# arduinoBasic.net
KiCad netlist of a schematic drawn in EAGLE
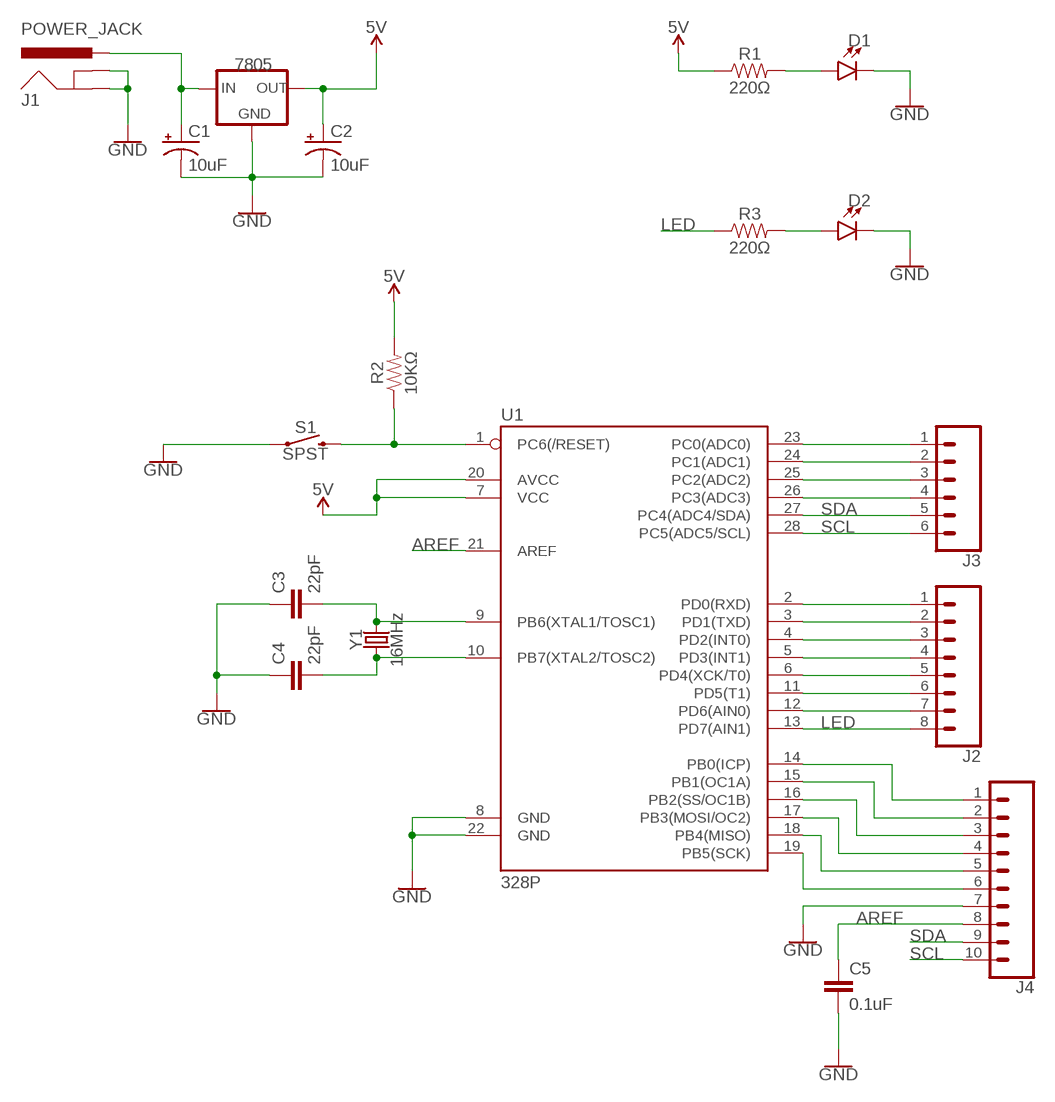
[diagram p0: schematic, sheet 1]

(export (version "E")
  (design (tool "Eeschema 10.0.6"))
  (components
    (comp (ref "7805")
      (value "V_REG_78XXSINK")
      (footprint "eagle-import:TO220-IGO")
      (libsource (lib "eagle-import") (part "V_REG_78XXSINK"))
    )
    (comp (ref "C1")
      (value "10uF")
      (footprint "eagle-import:CPOL-RADIAL-2.5MM-5MM")
      (libsource (lib "eagle-import") (part "10UF-POLAR-RADIAL-2.5MM-25V-20%"))
    )
    (comp (ref "C2")
      (value "10uF")
      (footprint "eagle-import:CPOL-RADIAL-2.5MM-5MM")
      (libsource (lib "eagle-import") (part "10UF-POLAR-RADIAL-2.5MM-25V-20%"))
    )
    (comp (ref "C3")
      (value "22pF")
      (footprint "eagle-import:CAP-PTH-2.54")
      (libsource (lib "eagle-import") (part "22PF-PTH-2.54MM-200V-5%"))
    )
    (comp (ref "C4")
      (value "22pF")
      (footprint "eagle-import:CAP-PTH-2.54")
      (libsource (lib "eagle-import") (part "22PF-PTH-2.54MM-200V-5%"))
    )
    (comp (ref "C5")
      (value "0.1uF")
      (footprint "eagle-import:CAP-PTH-SMALL-KIT")
      (libsource (lib "eagle-import") (part "0.1UF-KIT-EZ-50V-20%"))
    )
    (comp (ref "D1")
      (value "LED5MM")
      (footprint "eagle-import:LED_5MM")
      (libsource (lib "eagle-import") (part "LED5MM"))
    )
    (comp (ref "D2")
      (value "LED5MM")
      (footprint "eagle-import:LED_5MM")
      (libsource (lib "eagle-import") (part "LED5MM"))
    )
    (comp (ref "J1")
      (value "POWER_JACK")
      (footprint "eagle-import:POWER_JACK_PTH")
      (libsource (lib "eagle-import") (part "POWER_JACK"))
    )
    (comp (ref "J2")
      (value "CONN_08\"")
      (footprint "eagle-import:1X08")
      (libsource (lib "eagle-import") (part "CONN_08{dblquote}"))
    )
    (comp (ref "J3")
      (value "CONN_06SILK_FEMALE_PTH")
      (footprint "eagle-import:1X06")
      (libsource (lib "eagle-import") (part "CONN_06SILK_FEMALE_PTH"))
    )
    (comp (ref "J4")
      (value "CONN_10\"")
      (footprint "eagle-import:1X10")
      (libsource (lib "eagle-import") (part "CONN_10{dblquote}"))
    )
    (comp (ref "R1")
      (value "220Ω")
      (footprint "eagle-import:AXIAL-0.3")
      (libsource (lib "eagle-import") (part "RESISTORAXIAL-0.3"))
    )
    (comp (ref "R2")
      (value "10KΩ")
      (footprint "eagle-import:AXIAL-0.3")
      (libsource (lib "eagle-import") (part "RESISTORAXIAL-0.3"))
    )
    (comp (ref "R3")
      (value "220Ω")
      (footprint "eagle-import:AXIAL-0.3")
      (libsource (lib "eagle-import") (part "RESISTORAXIAL-0.3"))
    )
    (comp (ref "S1")
      (value "SPST")
      (footprint "eagle-import:TACTILE_SWITCH_PTH_12MM")
      (libsource (lib "eagle-import") (part "MOMENTARY-SWITCH-SPST-PTH-12MM"))
    )
    (comp (ref "U1")
      (value "328P")
      (footprint "eagle-import:DIP28")
      (libsource (lib "eagle-import") (part "ATMEGA328P_PDIP"))
    )
    (comp (ref "Y1")
      (value "16MHz")
      (footprint "eagle-import:HC49US")
      (libsource (lib "eagle-import") (part "CRYSTAL-16MHZPTH-HC49US"))
    )
  )
  (nets
    (net (code "1") (name "/AREF") (class "Default")
      (node (ref "C5") (pin "1") (pinfunction "1_1") (pintype "passive"))
      (node (ref "J4") (pin "8") (pinfunction "8_8") (pintype "passive"))
      (node (ref "U1") (pin "21") (pinfunction "AREF_21") (pintype "bidirectional"))
    )
    (net (code "2") (name "/LED") (class "Default")
      (node (ref "J2") (pin "8") (pinfunction "8_8") (pintype "passive"))
      (node (ref "R3") (pin "P$1") (pinfunction "1_P$1") (pintype "passive"))
      (node (ref "U1") (pin "13") (pinfunction "PD7(AIN1)_13") (pintype "bidirectional"))
    )
    (net (code "3") (name "/SCL") (class "Default")
      (node (ref "J3") (pin "6") (pinfunction "6_6") (pintype "passive"))
      (node (ref "J4") (pin "10") (pinfunction "10_10") (pintype "passive"))
      (node (ref "U1") (pin "28") (pinfunction "PC5(ADC5/SCL)_28") (pintype "bidirectional"))
    )
    (net (code "4") (name "/SDA") (class "Default")
      (node (ref "J3") (pin "5") (pinfunction "5_5") (pintype "passive"))
      (node (ref "J4") (pin "9") (pinfunction "9_9") (pintype "passive"))
      (node (ref "U1") (pin "27") (pinfunction "PC4(ADC4/SDA)_27") (pintype "bidirectional"))
    )
    (net (code "5") (name "5V") (class "Default")
      (node (ref "7805") (pin "OUT") (pinfunction "OUT_OUT") (pintype "passive"))
      (node (ref "C2") (pin "1") (pinfunction "+_1") (pintype "passive"))
      (node (ref "R1") (pin "P$1") (pinfunction "1_P$1") (pintype "passive"))
      (node (ref "R2") (pin "P$2") (pinfunction "2_P$2") (pintype "passive"))
      (node (ref "U1") (pin "20") (pinfunction "AVCC_20") (pintype "bidirectional"))
      (node (ref "U1") (pin "7") (pinfunction "VCC_7") (pintype "bidirectional"))
    )
    (net (code "6") (name "GND") (class "Default")
      (node (ref "7805") (pin "GND") (pinfunction "GND_GND") (pintype "input"))
      (node (ref "C1") (pin "2") (pinfunction "-_2") (pintype "passive"))
      (node (ref "C2") (pin "2") (pinfunction "-_2") (pintype "passive"))
      (node (ref "C3") (pin "1") (pinfunction "1_1") (pintype "passive"))
      (node (ref "C4") (pin "1") (pinfunction "1_1") (pintype "passive"))
      (node (ref "C5") (pin "2") (pinfunction "2_2") (pintype "passive"))
      (node (ref "D1") (pin "K") (pinfunction "C_K") (pintype "passive"))
      (node (ref "D2") (pin "K") (pinfunction "C_K") (pintype "passive"))
      (node (ref "J1") (pin "GND") (pinfunction "GND_GND") (pintype "bidirectional"))
      (node (ref "J1") (pin "GNDBREAK") (pinfunction "GNDBREAK_GNDBREAK") (pintype "bidirectional"))
      (node (ref "J4") (pin "7") (pinfunction "7_7") (pintype "passive"))
      (node (ref "S1") (pin "1") (pinfunction "1_1") (pintype "passive"))
      (node (ref "U1") (pin "22") (pinfunction "GND_22") (pintype "bidirectional"))
      (node (ref "U1") (pin "8") (pinfunction "GND_8") (pintype "bidirectional"))
    )
    (net (code "7") (name "Net-(C1-+)") (class "Default")
      (node (ref "7805") (pin "IN") (pinfunction "IN_IN") (pintype "input"))
      (node (ref "C1") (pin "1") (pinfunction "+_1") (pintype "passive"))
      (node (ref "J1") (pin "PWR") (pinfunction "PWR_PWR") (pintype "bidirectional"))
    )
    (net (code "8") (name "Net-(R1-2)") (class "Default")
      (node (ref "D1") (pin "A") (pinfunction "A_A") (pintype "passive"))
      (node (ref "R1") (pin "P$2") (pinfunction "2_P$2") (pintype "passive"))
    )
    (net (code "9") (name "Net-(R2-1)") (class "Default")
      (node (ref "R2") (pin "P$1") (pinfunction "1_P$1") (pintype "passive"))
      (node (ref "S1") (pin "3") (pinfunction "2_3") (pintype "passive"))
      (node (ref "U1") (pin "1") (pinfunction "PC6(/RESET)_1") (pintype "bidirectional"))
    )
    (net (code "10") (name "Net-(R3-2)") (class "Default")
      (node (ref "D2") (pin "A") (pinfunction "A_A") (pintype "passive"))
      (node (ref "R3") (pin "P$2") (pinfunction "2_P$2") (pintype "passive"))
    )
    (net (code "11") (name "Net-(U1-PB0(ICP))") (class "Default")
      (node (ref "J4") (pin "1") (pinfunction "1_1") (pintype "passive"))
      (node (ref "U1") (pin "14") (pinfunction "PB0(ICP)_14") (pintype "bidirectional"))
    )
    (net (code "12") (name "Net-(U1-PB1(OC1A))") (class "Default")
      (node (ref "J4") (pin "2") (pinfunction "2_2") (pintype "passive"))
      (node (ref "U1") (pin "15") (pinfunction "PB1(OC1A)_15") (pintype "bidirectional"))
    )
    (net (code "13") (name "Net-(U1-PB2(SS{slash}OC1B))") (class "Default")
      (node (ref "J4") (pin "3") (pinfunction "3_3") (pintype "passive"))
      (node (ref "U1") (pin "16") (pinfunction "PB2(SS/OC1B)_16") (pintype "bidirectional"))
    )
    (net (code "14") (name "Net-(U1-PB3(MOSI{slash}OC2))") (class "Default")
      (node (ref "J4") (pin "4") (pinfunction "4_4") (pintype "passive"))
      (node (ref "U1") (pin "17") (pinfunction "PB3(MOSI/OC2)_17") (pintype "bidirectional"))
    )
    (net (code "15") (name "Net-(U1-PB4(MISO))") (class "Default")
      (node (ref "J4") (pin "5") (pinfunction "5_5") (pintype "passive"))
      (node (ref "U1") (pin "18") (pinfunction "PB4(MISO)_18") (pintype "bidirectional"))
    )
    (net (code "16") (name "Net-(U1-PB5(SCK))") (class "Default")
      (node (ref "J4") (pin "6") (pinfunction "6_6") (pintype "passive"))
      (node (ref "U1") (pin "19") (pinfunction "PB5(SCK)_19") (pintype "bidirectional"))
    )
    (net (code "17") (name "Net-(U1-PB6(XTAL1{slash}TOSC1))") (class "Default")
      (node (ref "C3") (pin "2") (pinfunction "2_2") (pintype "passive"))
      (node (ref "U1") (pin "9") (pinfunction "PB6(XTAL1/TOSC1)_9") (pintype "bidirectional"))
      (node (ref "Y1") (pin "2") (pinfunction "2_2") (pintype "passive"))
    )
    (net (code "18") (name "Net-(U1-PB7(XTAL2{slash}TOSC2))") (class "Default")
      (node (ref "C4") (pin "2") (pinfunction "2_2") (pintype "passive"))
      (node (ref "U1") (pin "10") (pinfunction "PB7(XTAL2/TOSC2)_10") (pintype "bidirectional"))
      (node (ref "Y1") (pin "1") (pinfunction "1_1") (pintype "passive"))
    )
    (net (code "19") (name "Net-(U1-PC0(ADC0))") (class "Default")
      (node (ref "J3") (pin "1") (pinfunction "1_1") (pintype "passive"))
      (node (ref "U1") (pin "23") (pinfunction "PC0(ADC0)_23") (pintype "bidirectional"))
    )
    (net (code "20") (name "Net-(U1-PC1(ADC1))") (class "Default")
      (node (ref "J3") (pin "2") (pinfunction "2_2") (pintype "passive"))
      (node (ref "U1") (pin "24") (pinfunction "PC1(ADC1)_24") (pintype "bidirectional"))
    )
    (net (code "21") (name "Net-(U1-PC2(ADC2))") (class "Default")
      (node (ref "J3") (pin "3") (pinfunction "3_3") (pintype "passive"))
      (node (ref "U1") (pin "25") (pinfunction "PC2(ADC2)_25") (pintype "bidirectional"))
    )
    (net (code "22") (name "Net-(U1-PC3(ADC3))") (class "Default")
      (node (ref "J3") (pin "4") (pinfunction "4_4") (pintype "passive"))
      (node (ref "U1") (pin "26") (pinfunction "PC3(ADC3)_26") (pintype "bidirectional"))
    )
    (net (code "23") (name "Net-(U1-PD0(RXD))") (class "Default")
      (node (ref "J2") (pin "1") (pinfunction "1_1") (pintype "passive"))
      (node (ref "U1") (pin "2") (pinfunction "PD0(RXD)_2") (pintype "bidirectional"))
    )
    (net (code "24") (name "Net-(U1-PD1(TXD))") (class "Default")
      (node (ref "J2") (pin "2") (pinfunction "2_2") (pintype "passive"))
      (node (ref "U1") (pin "3") (pinfunction "PD1(TXD)_3") (pintype "bidirectional"))
    )
    (net (code "25") (name "Net-(U1-PD2(INT0))") (class "Default")
      (node (ref "J2") (pin "3") (pinfunction "3_3") (pintype "passive"))
      (node (ref "U1") (pin "4") (pinfunction "PD2(INT0)_4") (pintype "bidirectional"))
    )
    (net (code "26") (name "Net-(U1-PD3(INT1))") (class "Default")
      (node (ref "J2") (pin "4") (pinfunction "4_4") (pintype "passive"))
      (node (ref "U1") (pin "5") (pinfunction "PD3(INT1)_5") (pintype "bidirectional"))
    )
    (net (code "27") (name "Net-(U1-PD4(XCK{slash}T0))") (class "Default")
      (node (ref "J2") (pin "5") (pinfunction "5_5") (pintype "passive"))
      (node (ref "U1") (pin "6") (pinfunction "PD4(XCK/T0)_6") (pintype "bidirectional"))
    )
    (net (code "28") (name "Net-(U1-PD5(T1))") (class "Default")
      (node (ref "J2") (pin "6") (pinfunction "6_6") (pintype "passive"))
      (node (ref "U1") (pin "11") (pinfunction "PD5(T1)_11") (pintype "bidirectional"))
    )
    (net (code "29") (name "Net-(U1-PD6(AIN0))") (class "Default")
      (node (ref "J2") (pin "7") (pinfunction "7_7") (pintype "passive"))
      (node (ref "U1") (pin "12") (pinfunction "PD6(AIN0)_12") (pintype "bidirectional"))
    )
  )
)
